# driver-ha-v5.net
KiCad netlist of a schematic drawn in EAGLE
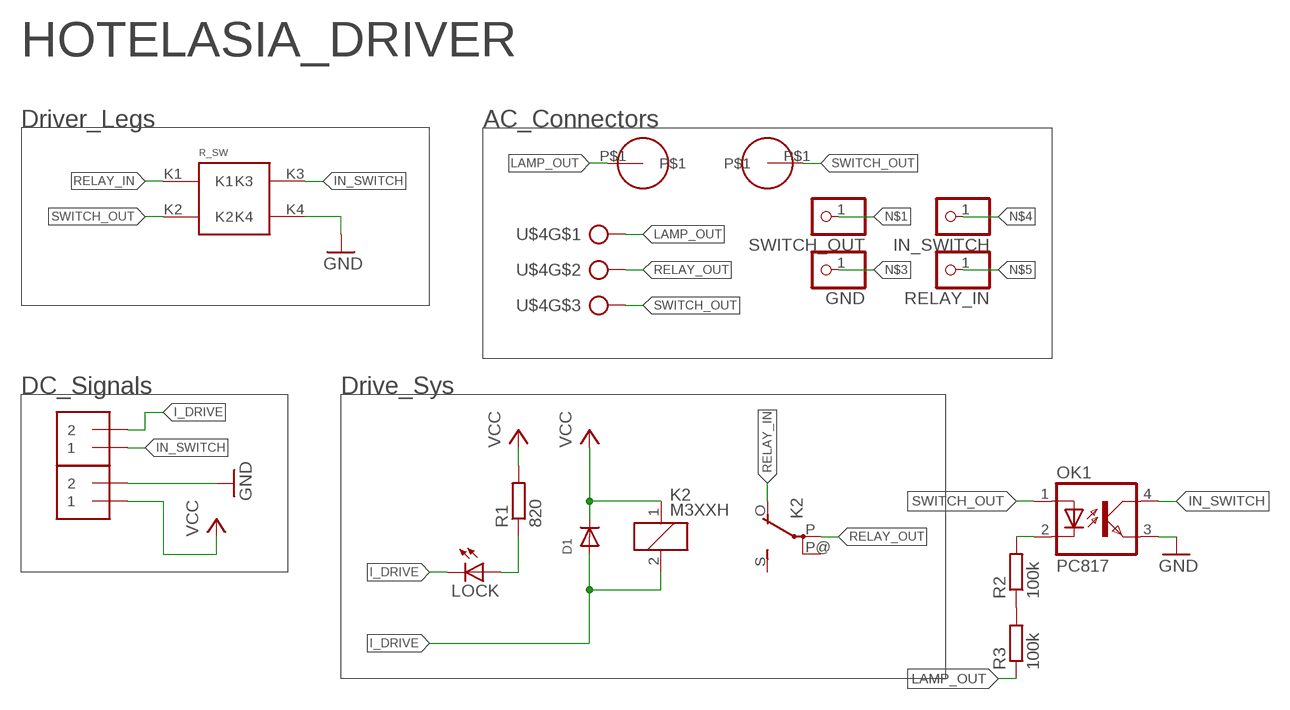
[diagram p0: schematic, sheet 1]

(export (version "E")
  (design (tool "Eeschema 10.0.6"))
  (components
    (comp (ref "D1")
      (value "DIODESMA")
      (footprint "eagle-import:SMADIODE")
      (libsource (lib "eagle-import") (part "DIODESMA"))
    )
    (comp (ref "GND")
      (value "PINHD-1X1")
      (footprint "eagle-import:1X01")
      (libsource (lib "eagle-import") (part "PINHD-1X1"))
    )
    (comp (ref "IN_SWITCH")
      (value "PINHD-1X1")
      (footprint "eagle-import:1X01")
      (libsource (lib "eagle-import") (part "PINHD-1X1"))
    )
    (comp (ref "J1")
      (value "1X2-3.5MM")
      (footprint "eagle-import:1X2-3.5MM")
      (libsource (lib "eagle-import") (part "1X2-3.5MM"))
    )
    (comp (ref "J2")
      (value "1X2-3.5MM")
      (footprint "eagle-import:1X2-3.5MM")
      (libsource (lib "eagle-import") (part "1X2-3.5MM"))
    )
    (comp (ref "K2")
      (value "M3XXH")
      (footprint "eagle-import:M3XXH")
      (libsource (lib "eagle-import") (part "M3XXH"))
    )
    (comp (ref "LOCK")
      (value "LED3MM")
      (footprint "eagle-import:LED3MM")
      (libsource (lib "eagle-import") (part "LED3MM"))
    )
    (comp (ref "OK1")
      (value "PC817")
      (footprint "eagle-import:DIL04")
      (fields (field (name "MPN") "PC817X4J000F"))
      (libsource (lib "eagle-import") (part "PC817"))
    )
    (comp (ref "PAD1")
      (value "ROOM_SWITCH")
      (footprint "eagle-import:ROOM_SWITCH")
      (libsource (lib "eagle-import") (part "ROOM_SWITCH"))
    )
    (comp (ref "R1")
      (value "820")
      (footprint "eagle-import:R0805")
      (libsource (lib "eagle-import") (part "R-EU_R0805"))
    )
    (comp (ref "R2")
      (value "100k")
      (footprint "eagle-import:R1206")
      (libsource (lib "eagle-import") (part "R-EU_R1206"))
    )
    (comp (ref "R3")
      (value "100k")
      (footprint "eagle-import:R1206")
      (libsource (lib "eagle-import") (part "R-EU_R1206"))
    )
    (comp (ref "RELAY_IN")
      (value "PINHD-1X1")
      (footprint "eagle-import:1X01")
      (libsource (lib "eagle-import") (part "PINHD-1X1"))
    )
    (comp (ref "SWITCH_OUT")
      (value "PINHD-1X1")
      (footprint "eagle-import:1X01")
      (libsource (lib "eagle-import") (part "PINHD-1X1"))
    )
    (comp (ref "U$1")
      (value "CONN-CABLE")
      (footprint "eagle-import:CONN-CABLE")
      (libsource (lib "eagle-import") (part "CONN-CABLE"))
    )
    (comp (ref "U$3")
      (value "CONN-CABLE")
      (footprint "eagle-import:CONN-CABLE")
      (libsource (lib "eagle-import") (part "CONN-CABLE"))
    )
    (comp (ref "U$4")
      (value "AK3003")
      (footprint "eagle-import:AK3003")
      (libsource (lib "eagle-import") (part "AK3003"))
    )
  )
  (nets
    (net (code "1") (name "GND") (class "Default")
      (node (ref "J2") (pin "2") (pinfunction "2_2") (pintype "passive"))
      (node (ref "OK1") (pin "3") (pinfunction "EMIT_3") (pintype "passive"))
      (node (ref "PAD1") (pin "K4") (pinfunction "K4_K4") (pintype "bidirectional"))
    )
    (net (code "2") (name "IN_SWITCH") (class "Default")
      (node (ref "J1") (pin "1") (pinfunction "1_1") (pintype "passive"))
      (node (ref "OK1") (pin "4") (pinfunction "COL_4") (pintype "passive"))
      (node (ref "PAD1") (pin "K3") (pinfunction "K3_K3") (pintype "bidirectional"))
    )
    (net (code "3") (name "I_DRIVE") (class "Default")
      (node (ref "D1") (pin "A") (pinfunction "A_A") (pintype "passive"))
      (node (ref "J1") (pin "2") (pinfunction "2_2") (pintype "passive"))
      (node (ref "K2") (pin "2") (pinfunction "2_2") (pintype "passive"))
      (node (ref "LOCK") (pin "K") (pinfunction "C_K") (pintype "passive"))
    )
    (net (code "4") (name "LAMP_OUT") (class "Default")
      (node (ref "R3") (pin "1") (pinfunction "1_1") (pintype "passive"))
      (node (ref "U$1") (pin "P$1") (pinfunction "P$1_P$1") (pintype "bidirectional"))
      (node (ref "U$4") (pin "1") (pinfunction "KL_1") (pintype "passive"))
    )
    (net (code "5") (name "N$1") (class "Default")
      (node (ref "SWITCH_OUT") (pin "1") (pinfunction "1_1") (pintype "passive"))
    )
    (net (code "6") (name "N$3") (class "Default")
      (node (ref "GND") (pin "1") (pinfunction "1_1") (pintype "passive"))
    )
    (net (code "7") (name "N$4") (class "Default")
      (node (ref "IN_SWITCH") (pin "1") (pinfunction "1_1") (pintype "passive"))
    )
    (net (code "8") (name "N$5") (class "Default")
      (node (ref "RELAY_IN") (pin "1") (pinfunction "1_1") (pintype "passive"))
    )
    (net (code "9") (name "Net-(LOCK-PadA)") (class "Default")
      (node (ref "LOCK") (pin "A") (pinfunction "A_A") (pintype "passive"))
      (node (ref "R1") (pin "1") (pinfunction "1_1") (pintype "passive"))
    )
    (net (code "10") (name "Net-(OK1-C)") (class "Default")
      (node (ref "OK1") (pin "2") (pinfunction "C_2") (pintype "passive"))
      (node (ref "R2") (pin "2") (pinfunction "2_2") (pintype "passive"))
    )
    (net (code "11") (name "Net-(R2-Pad1)") (class "Default")
      (node (ref "R2") (pin "1") (pinfunction "1_1") (pintype "passive"))
      (node (ref "R3") (pin "2") (pinfunction "2_2") (pintype "passive"))
    )
    (net (code "12") (name "RELAY_IN") (class "Default")
      (node (ref "K2") (pin "O") (pinfunction "O_O") (pintype "passive"))
      (node (ref "PAD1") (pin "K1") (pinfunction "K1_K1") (pintype "bidirectional"))
    )
    (net (code "13") (name "RELAY_OUT") (class "Default")
      (node (ref "K2") (pin "P") (pinfunction "P_P") (pintype "passive"))
      (node (ref "U$4") (pin "2") (pinfunction "KL_2") (pintype "passive"))
    )
    (net (code "14") (name "SWITCH_OUT") (class "Default")
      (node (ref "OK1") (pin "1") (pinfunction "A_1") (pintype "passive"))
      (node (ref "PAD1") (pin "K2") (pinfunction "K2_K2") (pintype "bidirectional"))
      (node (ref "U$3") (pin "P$1") (pinfunction "P$1_P$1") (pintype "bidirectional"))
      (node (ref "U$4") (pin "3") (pinfunction "KL_3") (pintype "passive"))
    )
    (net (code "15") (name "VCC") (class "Default")
      (node (ref "D1") (pin "C") (pinfunction "C_C") (pintype "passive"))
      (node (ref "J2") (pin "1") (pinfunction "1_1") (pintype "passive"))
      (node (ref "K2") (pin "1") (pinfunction "1_1") (pintype "passive"))
      (node (ref "R1") (pin "2") (pinfunction "2_2") (pintype "passive"))
    )
    (net (code "16") (name "unconnected-(K2-PadS)") (class "Default")
      (node (ref "K2") (pin "S") (pinfunction "S_S") (pintype "passive"))
    )
    (net (code "17") (name "unconnected-(K2B-P-PadP@)") (class "Default")
      (node (ref "K2") (pin "P@") (pinfunction "P_P@") (pintype "passive"))
    )
  )
)
